# fabflash-mk1.net
KiCad netlist of a schematic drawn in EAGLE
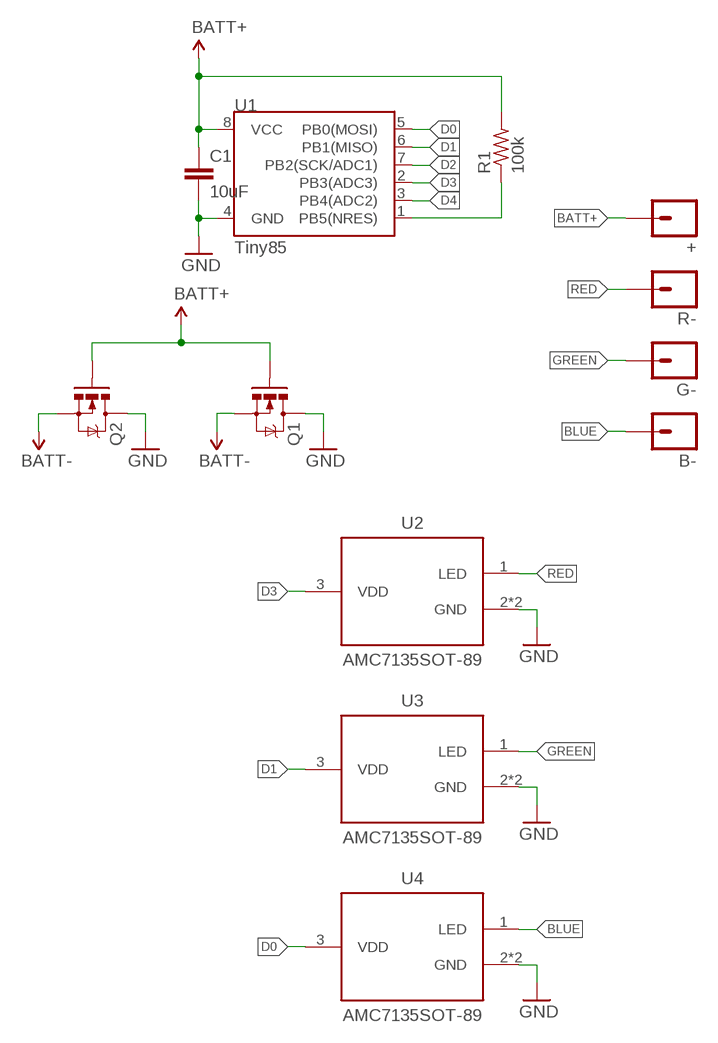
[diagram p0: schematic, sheet 1]

(export (version "E")
  (design (tool "Eeschema 10.0.6"))
  (components
    (comp (ref "+")
      (value "M01PTH-1.2MM-NS")
      (footprint "eagle-import:1X01-1.2MM-NS")
      (libsource (lib "eagle-import") (part "M01PTH-1.2MM-NS"))
    )
    (comp (ref "B-")
      (value "M01PTH-1.2MM-NS")
      (footprint "eagle-import:1X01-1.2MM-NS")
      (libsource (lib "eagle-import") (part "M01PTH-1.2MM-NS"))
    )
    (comp (ref "C1")
      (value "10uF")
      (footprint "eagle-import:C0603")
      (libsource (lib "eagle-import") (part "CAPACITOR-CERAMICC0603"))
    )
    (comp (ref "G-")
      (value "M01PTH-1.2MM-NS")
      (footprint "eagle-import:1X01-1.2MM-NS")
      (libsource (lib "eagle-import") (part "M01PTH-1.2MM-NS"))
    )
    (comp (ref "Q1")
      (value "MOSFET-NCHANNELIRLML2502")
      (footprint "eagle-import:SOT23")
      (libsource (lib "eagle-import") (part "MOSFET-NCHANNELIRLML2502"))
    )
    (comp (ref "Q2")
      (value "MOSFET-NCHANNELIRLML2502")
      (footprint "eagle-import:SOT23")
      (libsource (lib "eagle-import") (part "MOSFET-NCHANNELIRLML2502"))
    )
    (comp (ref "R-")
      (value "M01PTH-1.2MM-NS")
      (footprint "eagle-import:1X01-1.2MM-NS")
      (libsource (lib "eagle-import") (part "M01PTH-1.2MM-NS"))
    )
    (comp (ref "R1")
      (value "100k")
      (footprint "eagle-import:R0603")
      (libsource (lib "eagle-import") (part "RESISTORR0603"))
    )
    (comp (ref "U1")
      (value "Tiny85")
      (footprint "eagle-import:SO08-EIAJ")
      (libsource (lib "eagle-import") (part "ATTINY45TINY85-20-SMT"))
    )
    (comp (ref "U2")
      (value "AMC7135SOT-89")
      (footprint "eagle-import:SOT89")
      (libsource (lib "eagle-import") (part "AMC7135SOT-89"))
    )
    (comp (ref "U3")
      (value "AMC7135SOT-89")
      (footprint "eagle-import:SOT89")
      (libsource (lib "eagle-import") (part "AMC7135SOT-89"))
    )
    (comp (ref "U4")
      (value "AMC7135SOT-89")
      (footprint "eagle-import:SOT89")
      (libsource (lib "eagle-import") (part "AMC7135SOT-89"))
    )
  )
  (nets
    (net (code "1") (name "BATT+") (class "Default")
      (node (ref "+") (pin "P$1") (pinfunction "1_P$1") (pintype "passive"))
      (node (ref "C1") (pin "1") (pinfunction "1_1") (pintype "passive"))
      (node (ref "Q1") (pin "1") (pinfunction "G_1") (pintype "passive"))
      (node (ref "Q2") (pin "1") (pinfunction "G_1") (pintype "passive"))
      (node (ref "R1") (pin "2") (pinfunction "2_2") (pintype "passive"))
      (node (ref "U1") (pin "8") (pinfunction "VCC_8") (pintype "bidirectional"))
    )
    (net (code "2") (name "BATT-") (class "Default")
      (node (ref "Q1") (pin "2") (pinfunction "S_2") (pintype "passive"))
      (node (ref "Q2") (pin "2") (pinfunction "S_2") (pintype "passive"))
    )
    (net (code "3") (name "BLUE") (class "Default")
      (node (ref "B-") (pin "P$1") (pinfunction "1_P$1") (pintype "passive"))
      (node (ref "U4") (pin "1") (pinfunction "LED_1") (pintype "bidirectional"))
    )
    (net (code "4") (name "D0") (class "Default")
      (node (ref "U1") (pin "5") (pinfunction "PB0(MOSI)_5") (pintype "bidirectional"))
      (node (ref "U4") (pin "3") (pinfunction "VDD_3") (pintype "bidirectional"))
    )
    (net (code "5") (name "D1") (class "Default")
      (node (ref "U1") (pin "6") (pinfunction "PB1(MISO)_6") (pintype "bidirectional"))
      (node (ref "U3") (pin "3") (pinfunction "VDD_3") (pintype "bidirectional"))
    )
    (net (code "6") (name "D2") (class "Default")
      (node (ref "U1") (pin "7") (pinfunction "PB2(SCK/ADC1)_7") (pintype "bidirectional"))
    )
    (net (code "7") (name "D3") (class "Default")
      (node (ref "U1") (pin "2") (pinfunction "PB3(ADC3)_2") (pintype "bidirectional"))
      (node (ref "U2") (pin "3") (pinfunction "VDD_3") (pintype "bidirectional"))
    )
    (net (code "8") (name "D4") (class "Default")
      (node (ref "U1") (pin "3") (pinfunction "PB4(ADC2)_3") (pintype "bidirectional"))
    )
    (net (code "9") (name "GND") (class "Default")
      (node (ref "C1") (pin "2") (pinfunction "2_2") (pintype "passive"))
      (node (ref "Q1") (pin "3") (pinfunction "D_3") (pintype "passive"))
      (node (ref "Q2") (pin "3") (pinfunction "D_3") (pintype "passive"))
      (node (ref "U1") (pin "4") (pinfunction "GND_4") (pintype "bidirectional"))
      (node (ref "U2") (pin "2") (pinfunction "GND_2") (pintype "bidirectional"))
      (node (ref "U2") (pin "4") (pinfunction "GND_4") (pintype "bidirectional"))
      (node (ref "U3") (pin "2") (pinfunction "GND_2") (pintype "bidirectional"))
      (node (ref "U3") (pin "4") (pinfunction "GND_4") (pintype "bidirectional"))
      (node (ref "U4") (pin "2") (pinfunction "GND_2") (pintype "bidirectional"))
      (node (ref "U4") (pin "4") (pinfunction "GND_4") (pintype "bidirectional"))
    )
    (net (code "10") (name "GREEN") (class "Default")
      (node (ref "G-") (pin "P$1") (pinfunction "1_P$1") (pintype "passive"))
      (node (ref "U3") (pin "1") (pinfunction "LED_1") (pintype "bidirectional"))
    )
    (net (code "11") (name "Net-(U1-PB5(NRES))") (class "Default")
      (node (ref "R1") (pin "1") (pinfunction "1_1") (pintype "passive"))
      (node (ref "U1") (pin "1") (pinfunction "PB5(NRES)_1") (pintype "bidirectional"))
    )
    (net (code "12") (name "RED") (class "Default")
      (node (ref "R-") (pin "P$1") (pinfunction "1_P$1") (pintype "passive"))
      (node (ref "U2") (pin "1") (pinfunction "LED_1") (pintype "bidirectional"))
    )
  )
)
